# zikburner-r1.net
KiCad netlist of a schematic drawn in EAGLE
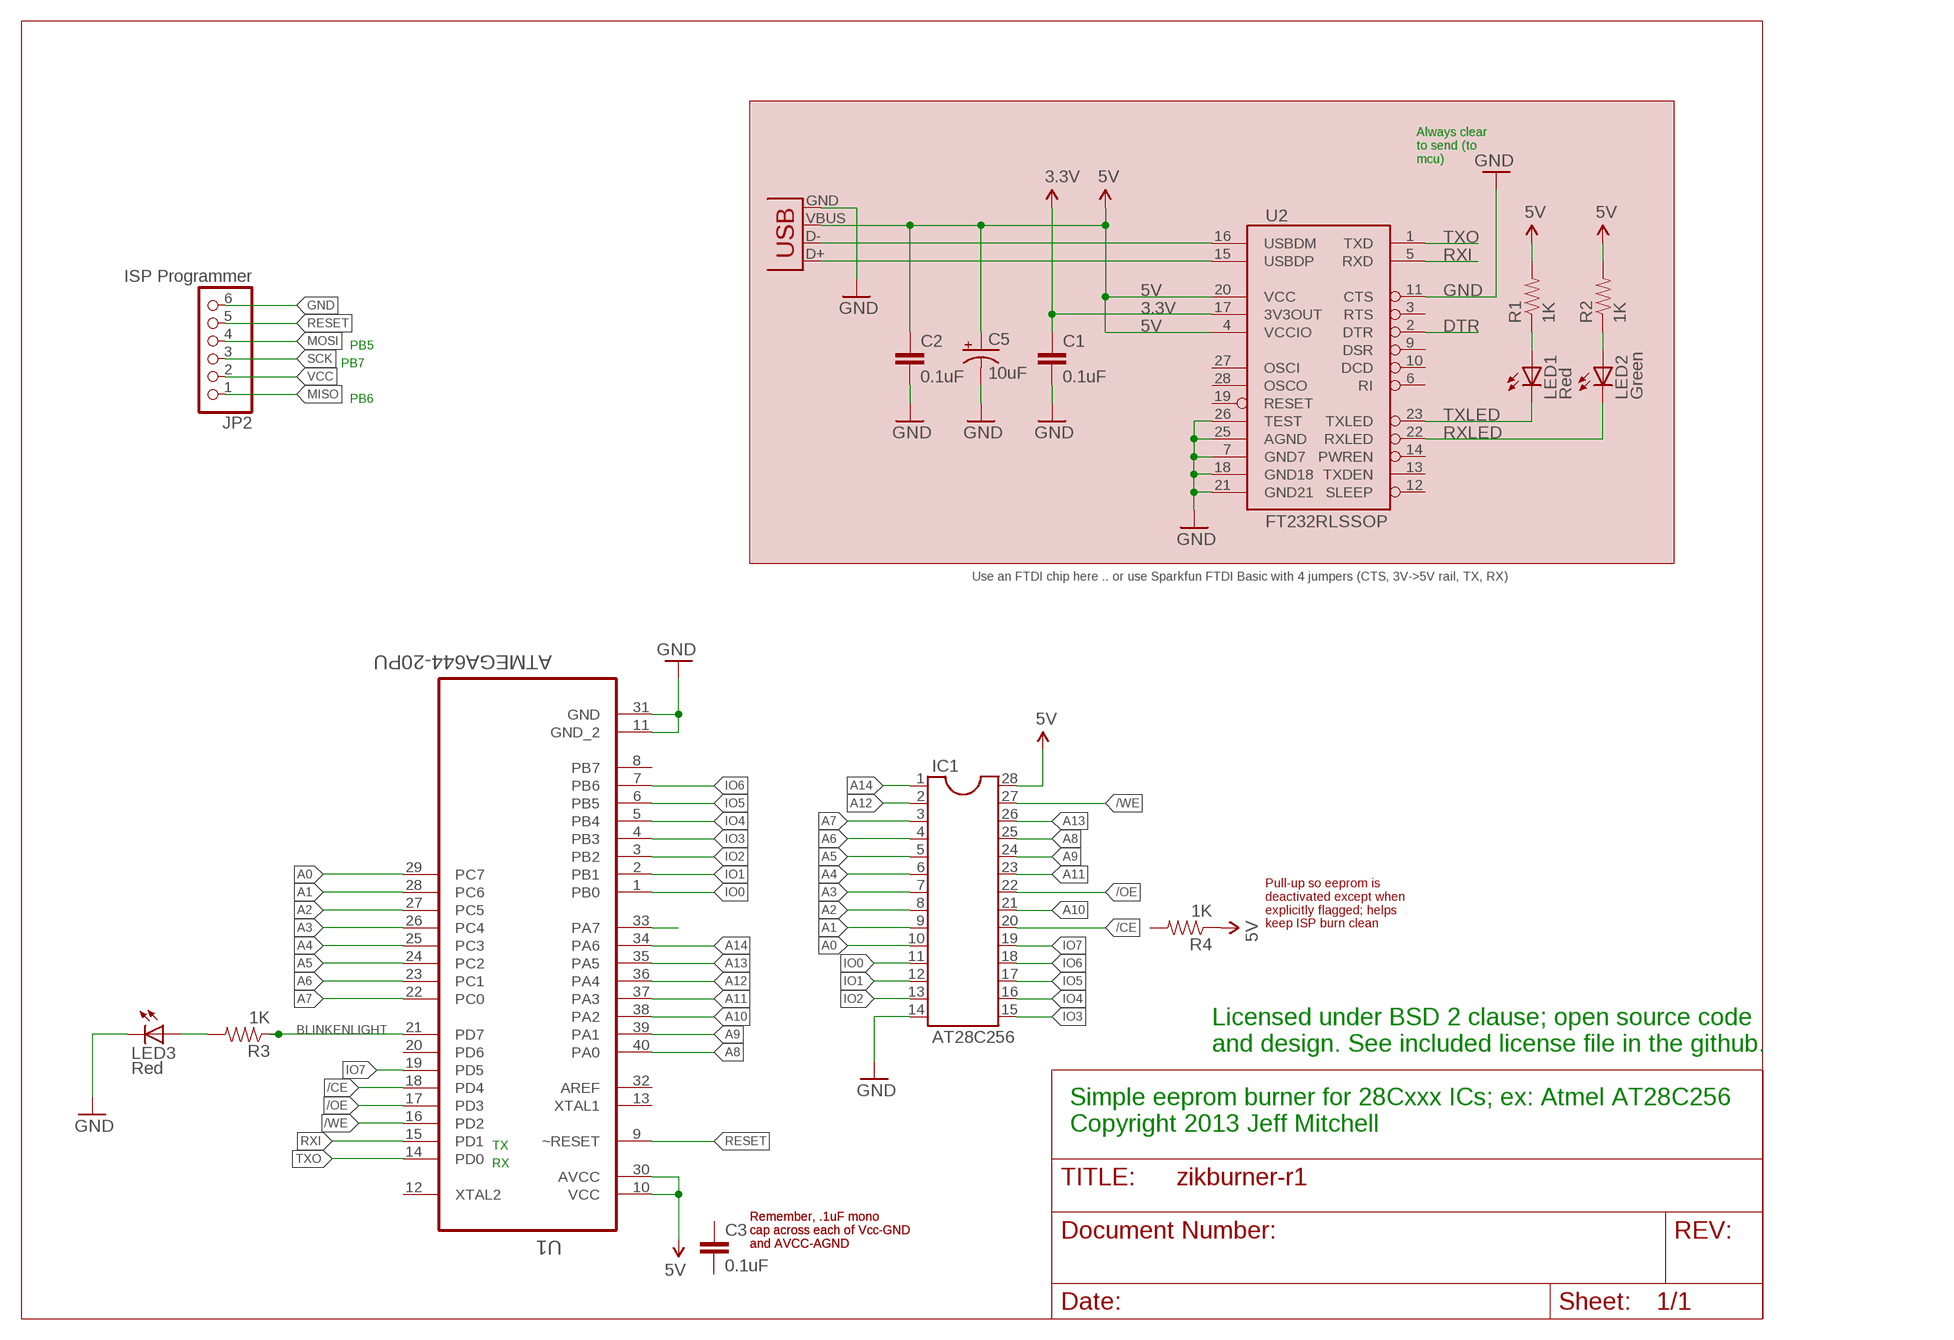
[diagram p0: schematic, sheet 1]

(export (version "E")
  (design (tool "Eeschema 10.0.6"))
  (components
    (comp (ref "C1")
      (value "0.1uF")
      (footprint "eagle-import:0402-CAP")
      (libsource (lib "eagle-import") (part "CAP0402-CAP"))
    )
    (comp (ref "C2")
      (value "0.1uF")
      (footprint "eagle-import:0402-CAP")
      (libsource (lib "eagle-import") (part "CAP0402-CAP"))
    )
    (comp (ref "C3")
      (value "0.1uF")
      (footprint "eagle-import:0402-CAP")
      (libsource (lib "eagle-import") (part "CAP0402-CAP"))
    )
    (comp (ref "C5")
      (value "10uF")
      (footprint "eagle-import:EIA3216")
      (libsource (lib "eagle-import") (part "CAP_POL1206"))
    )
    (comp (ref "IC1")
      (value "AT28C256")
      (footprint "eagle-import:DIL28-6")
      (libsource (lib "eagle-import") (part "DIL28"))
    )
    (comp (ref "JP2")
      (value "ISP Programmer")
      (footprint "eagle-import:1X06")
      (libsource (lib "eagle-import") (part "PINHD-1X6"))
    )
    (comp (ref "LED1")
      (value "Red")
      (footprint "eagle-import:LED-0603")
      (libsource (lib "eagle-import") (part "LED0603"))
    )
    (comp (ref "LED2")
      (value "Green")
      (footprint "eagle-import:LED-0603")
      (libsource (lib "eagle-import") (part "LED0603"))
    )
    (comp (ref "LED3")
      (value "Red")
      (footprint "eagle-import:LED-0603")
      (libsource (lib "eagle-import") (part "LED0603"))
    )
    (comp (ref "R1")
      (value "1K")
      (footprint "eagle-import:0402-RES")
      (libsource (lib "eagle-import") (part "RESISTOR0402-RES"))
    )
    (comp (ref "R2")
      (value "1K")
      (footprint "eagle-import:0402-RES")
      (libsource (lib "eagle-import") (part "RESISTOR0402-RES"))
    )
    (comp (ref "R3")
      (value "1K")
      (footprint "eagle-import:0402-RES")
      (libsource (lib "eagle-import") (part "RESISTOR0402-RES"))
    )
    (comp (ref "R4")
      (value "1K")
      (footprint "eagle-import:0402-RES")
      (libsource (lib "eagle-import") (part "RESISTOR0402-RES"))
    )
    (comp (ref "U1")
      (value "ATMEGA644-20PU")
      (footprint "eagle-import:DIP254P1524X482-40")
      (libsource (lib "eagle-import") (part "ATMEGA644-20PU"))
    )
    (comp (ref "U2")
      (value "FT232RLSSOP")
      (footprint "eagle-import:SSOP28DB")
      (libsource (lib "eagle-import") (part "FT232RLSSOP"))
    )
    (comp (ref "X2")
      (value "USB-SMD-NS")
      (footprint "eagle-import:USB-MINIB-NOSTOP")
      (libsource (lib "eagle-import") (part "USB-SMD-NS"))
    )
  )
  (nets
    (net (code "1") (name "/BLINKENLIGHT") (class "Default")
      (node (ref "R3") (pin "1") (pinfunction "1_1") (pintype "passive"))
      (node (ref "U1") (pin "21") (pinfunction "PD7_21") (pintype "bidirectional"))
    )
    (net (code "2") (name "/DTR") (class "Default")
      (node (ref "U2") (pin "2") (pinfunction "DTR_2") (pintype "output"))
    )
    (net (code "3") (name "/RXLED") (class "Default")
      (node (ref "LED2") (pin "C") (pinfunction "C_C") (pintype "passive"))
      (node (ref "U2") (pin "22") (pinfunction "RXLED_22") (pintype "input"))
    )
    (net (code "4") (name "/TXLED") (class "Default")
      (node (ref "LED1") (pin "C") (pinfunction "C_C") (pintype "passive"))
      (node (ref "U2") (pin "23") (pinfunction "TXLED_23") (pintype "input"))
    )
    (net (code "5") (name "3.3V") (class "Default")
      (node (ref "C1") (pin "1") (pinfunction "1_1") (pintype "passive"))
      (node (ref "U2") (pin "17") (pinfunction "3V3OUT_17") (pintype "output"))
    )
    (net (code "6") (name "5V") (class "Default")
      (node (ref "C2") (pin "1") (pinfunction "1_1") (pintype "passive"))
      (node (ref "C5") (pin "A") (pinfunction "+_A") (pintype "passive"))
      (node (ref "IC1") (pin "28") (pinfunction "28_28") (pintype "passive"))
      (node (ref "R1") (pin "2") (pinfunction "2_2") (pintype "passive"))
      (node (ref "R2") (pin "2") (pinfunction "2_2") (pintype "passive"))
      (node (ref "R4") (pin "1") (pinfunction "1_1") (pintype "passive"))
      (node (ref "U1") (pin "10") (pinfunction "VCC_10") (pintype "power_in"))
      (node (ref "U1") (pin "30") (pinfunction "AVCC_30") (pintype "power_in"))
      (node (ref "U2") (pin "20") (pinfunction "VCC_20") (pintype "power_in"))
      (node (ref "U2") (pin "4") (pinfunction "VCCIO_4") (pintype "power_in"))
      (node (ref "X2") (pin "VBUS") (pinfunction "VBUS_VBUS") (pintype "bidirectional"))
    )
    (net (code "7") (name "A0") (class "Default")
      (node (ref "IC1") (pin "10") (pinfunction "10_10") (pintype "passive"))
      (node (ref "U1") (pin "29") (pinfunction "PC7_29") (pintype "bidirectional"))
    )
    (net (code "8") (name "A1") (class "Default")
      (node (ref "IC1") (pin "9") (pinfunction "9_9") (pintype "passive"))
      (node (ref "U1") (pin "28") (pinfunction "PC6_28") (pintype "bidirectional"))
    )
    (net (code "9") (name "A2") (class "Default")
      (node (ref "IC1") (pin "8") (pinfunction "8_8") (pintype "passive"))
      (node (ref "U1") (pin "27") (pinfunction "PC5_27") (pintype "bidirectional"))
    )
    (net (code "10") (name "A3") (class "Default")
      (node (ref "IC1") (pin "7") (pinfunction "7_7") (pintype "passive"))
      (node (ref "U1") (pin "26") (pinfunction "PC4_26") (pintype "bidirectional"))
    )
    (net (code "11") (name "A4") (class "Default")
      (node (ref "IC1") (pin "6") (pinfunction "6_6") (pintype "passive"))
      (node (ref "U1") (pin "25") (pinfunction "PC3_25") (pintype "bidirectional"))
    )
    (net (code "12") (name "A5") (class "Default")
      (node (ref "IC1") (pin "5") (pinfunction "5_5") (pintype "passive"))
      (node (ref "U1") (pin "24") (pinfunction "PC2_24") (pintype "bidirectional"))
    )
    (net (code "13") (name "A6") (class "Default")
      (node (ref "IC1") (pin "4") (pinfunction "4_4") (pintype "passive"))
      (node (ref "U1") (pin "23") (pinfunction "PC1_23") (pintype "bidirectional"))
    )
    (net (code "14") (name "A7") (class "Default")
      (node (ref "IC1") (pin "3") (pinfunction "3_3") (pintype "passive"))
      (node (ref "U1") (pin "22") (pinfunction "PC0_22") (pintype "bidirectional"))
    )
    (net (code "15") (name "A8") (class "Default")
      (node (ref "IC1") (pin "25") (pinfunction "25_25") (pintype "passive"))
      (node (ref "U1") (pin "40") (pinfunction "PA0_40") (pintype "bidirectional"))
    )
    (net (code "16") (name "A9") (class "Default")
      (node (ref "IC1") (pin "24") (pinfunction "24_24") (pintype "passive"))
      (node (ref "U1") (pin "39") (pinfunction "PA1_39") (pintype "bidirectional"))
    )
    (net (code "17") (name "A10") (class "Default")
      (node (ref "IC1") (pin "21") (pinfunction "21_21") (pintype "passive"))
      (node (ref "U1") (pin "38") (pinfunction "PA2_38") (pintype "bidirectional"))
    )
    (net (code "18") (name "A11") (class "Default")
      (node (ref "IC1") (pin "23") (pinfunction "23_23") (pintype "passive"))
      (node (ref "U1") (pin "37") (pinfunction "PA3_37") (pintype "bidirectional"))
    )
    (net (code "19") (name "A12") (class "Default")
      (node (ref "IC1") (pin "2") (pinfunction "2_2") (pintype "passive"))
      (node (ref "U1") (pin "36") (pinfunction "PA4_36") (pintype "bidirectional"))
    )
    (net (code "20") (name "A13") (class "Default")
      (node (ref "IC1") (pin "26") (pinfunction "26_26") (pintype "passive"))
      (node (ref "U1") (pin "35") (pinfunction "PA5_35") (pintype "bidirectional"))
    )
    (net (code "21") (name "A14") (class "Default")
      (node (ref "IC1") (pin "1") (pinfunction "1_1") (pintype "passive"))
      (node (ref "U1") (pin "34") (pinfunction "PA6_34") (pintype "bidirectional"))
    )
    (net (code "22") (name "GND") (class "Default")
      (node (ref "C1") (pin "2") (pinfunction "2_2") (pintype "passive"))
      (node (ref "C2") (pin "2") (pinfunction "2_2") (pintype "passive"))
      (node (ref "C5") (pin "C") (pinfunction "-_C") (pintype "passive"))
      (node (ref "IC1") (pin "14") (pinfunction "14_14") (pintype "passive"))
      (node (ref "JP2") (pin "6") (pinfunction "6_6") (pintype "passive"))
      (node (ref "LED3") (pin "C") (pinfunction "C_C") (pintype "passive"))
      (node (ref "U1") (pin "11") (pinfunction "GND_2_11") (pintype "passive"))
      (node (ref "U1") (pin "31") (pinfunction "GND_31") (pintype "passive"))
      (node (ref "U2") (pin "11") (pinfunction "CTS_11") (pintype "input"))
      (node (ref "U2") (pin "18") (pinfunction "GND18_18") (pintype "power_in"))
      (node (ref "U2") (pin "21") (pinfunction "GND21_21") (pintype "power_in"))
      (node (ref "U2") (pin "25") (pinfunction "AGND_25") (pintype "power_in"))
      (node (ref "U2") (pin "26") (pinfunction "TEST_26") (pintype "input"))
      (node (ref "U2") (pin "7") (pinfunction "GND7_7") (pintype "power_in"))
      (node (ref "X2") (pin "GND") (pinfunction "GND_GND") (pintype "bidirectional"))
    )
    (net (code "23") (name "IO0") (class "Default")
      (node (ref "IC1") (pin "11") (pinfunction "11_11") (pintype "passive"))
      (node (ref "U1") (pin "1") (pinfunction "PB0_1") (pintype "bidirectional"))
    )
    (net (code "24") (name "IO1") (class "Default")
      (node (ref "IC1") (pin "12") (pinfunction "12_12") (pintype "passive"))
      (node (ref "U1") (pin "2") (pinfunction "PB1_2") (pintype "bidirectional"))
    )
    (net (code "25") (name "IO2") (class "Default")
      (node (ref "IC1") (pin "13") (pinfunction "13_13") (pintype "passive"))
      (node (ref "U1") (pin "3") (pinfunction "PB2_3") (pintype "bidirectional"))
    )
    (net (code "26") (name "IO3") (class "Default")
      (node (ref "IC1") (pin "15") (pinfunction "15_15") (pintype "passive"))
      (node (ref "U1") (pin "4") (pinfunction "PB3_4") (pintype "bidirectional"))
    )
    (net (code "27") (name "IO4") (class "Default")
      (node (ref "IC1") (pin "16") (pinfunction "16_16") (pintype "passive"))
      (node (ref "U1") (pin "5") (pinfunction "PB4_5") (pintype "bidirectional"))
    )
    (net (code "28") (name "IO5") (class "Default")
      (node (ref "IC1") (pin "17") (pinfunction "17_17") (pintype "passive"))
      (node (ref "U1") (pin "6") (pinfunction "PB5_6") (pintype "bidirectional"))
    )
    (net (code "29") (name "IO6") (class "Default")
      (node (ref "IC1") (pin "18") (pinfunction "18_18") (pintype "passive"))
      (node (ref "U1") (pin "7") (pinfunction "PB6_7") (pintype "bidirectional"))
    )
    (net (code "30") (name "IO7") (class "Default")
      (node (ref "IC1") (pin "19") (pinfunction "19_19") (pintype "passive"))
      (node (ref "U1") (pin "19") (pinfunction "PD5_19") (pintype "bidirectional"))
    )
    (net (code "31") (name "MISO") (class "Default")
      (node (ref "JP2") (pin "1") (pinfunction "1_1") (pintype "passive"))
    )
    (net (code "32") (name "MOSI") (class "Default")
      (node (ref "JP2") (pin "4") (pinfunction "4_4") (pintype "passive"))
    )
    (net (code "33") (name "Net-(LED1-PadA)") (class "Default")
      (node (ref "LED1") (pin "A") (pinfunction "A_A") (pintype "passive"))
      (node (ref "R1") (pin "1") (pinfunction "1_1") (pintype "passive"))
    )
    (net (code "34") (name "Net-(LED2-PadA)") (class "Default")
      (node (ref "LED2") (pin "A") (pinfunction "A_A") (pintype "passive"))
      (node (ref "R2") (pin "1") (pinfunction "1_1") (pintype "passive"))
    )
    (net (code "35") (name "Net-(LED3-PadA)") (class "Default")
      (node (ref "LED3") (pin "A") (pinfunction "A_A") (pintype "passive"))
      (node (ref "R3") (pin "2") (pinfunction "2_2") (pintype "passive"))
    )
    (net (code "36") (name "Net-(U2-USBDM)") (class "Default")
      (node (ref "U2") (pin "16") (pinfunction "USBDM_16") (pintype "bidirectional"))
      (node (ref "X2") (pin "D-") (pinfunction "D-_D-") (pintype "bidirectional"))
    )
    (net (code "37") (name "Net-(U2-USBDP)") (class "Default")
      (node (ref "U2") (pin "15") (pinfunction "USBDP_15") (pintype "bidirectional"))
      (node (ref "X2") (pin "D+") (pinfunction "D+_D+") (pintype "bidirectional"))
    )
    (net (code "38") (name "RESET") (class "Default")
      (node (ref "JP2") (pin "5") (pinfunction "5_5") (pintype "passive"))
      (node (ref "U1") (pin "9") (pinfunction "~{RESET}_9") (pintype "input"))
    )
    (net (code "39") (name "RXI") (class "Default")
      (node (ref "U1") (pin "15") (pinfunction "PD1_15") (pintype "bidirectional"))
      (node (ref "U2") (pin "5") (pinfunction "RXD_5") (pintype "input"))
    )
    (net (code "40") (name "SCK") (class "Default")
      (node (ref "JP2") (pin "3") (pinfunction "3_3") (pintype "passive"))
    )
    (net (code "41") (name "TXO") (class "Default")
      (node (ref "U1") (pin "14") (pinfunction "PD0_14") (pintype "bidirectional"))
      (node (ref "U2") (pin "1") (pinfunction "TXD_1") (pintype "output"))
    )
    (net (code "42") (name "VCC") (class "Default")
      (node (ref "JP2") (pin "2") (pinfunction "2_2") (pintype "passive"))
    )
    (net (code "43") (name "unconnected-(C3-Pad1)") (class "Default")
      (node (ref "C3") (pin "1") (pinfunction "1_1") (pintype "passive"))
    )
    (net (code "44") (name "unconnected-(C3-Pad2)") (class "Default")
      (node (ref "C3") (pin "2") (pinfunction "2_2") (pintype "passive"))
    )
    (net (code "45") (name "unconnected-(R4-Pad2)") (class "Default")
      (node (ref "R4") (pin "2") (pinfunction "2_2") (pintype "passive"))
    )
    (net (code "46") (name "unconnected-(U1-AREF-Pad32)") (class "Default")
      (node (ref "U1") (pin "32") (pinfunction "AREF_32") (pintype "input"))
    )
    (net (code "47") (name "unconnected-(U1-PA7-Pad33)") (class "Default")
      (node (ref "U1") (pin "33") (pinfunction "PA7_33") (pintype "bidirectional"))
    )
    (net (code "48") (name "unconnected-(U1-PB7-Pad8)") (class "Default")
      (node (ref "U1") (pin "8") (pinfunction "PB7_8") (pintype "bidirectional"))
    )
    (net (code "49") (name "unconnected-(U1-PD6-Pad20)") (class "Default")
      (node (ref "U1") (pin "20") (pinfunction "PD6_20") (pintype "bidirectional"))
    )
    (net (code "50") (name "unconnected-(U1-XTAL1-Pad13)") (class "Default")
      (node (ref "U1") (pin "13") (pinfunction "XTAL1_13") (pintype "input"))
    )
    (net (code "51") (name "unconnected-(U1-XTAL2-Pad12)") (class "Default")
      (node (ref "U1") (pin "12") (pinfunction "XTAL2_12") (pintype "output"))
    )
    (net (code "52") (name "unconnected-(U2-DCD-Pad10)") (class "Default")
      (node (ref "U2") (pin "10") (pinfunction "DCD_10") (pintype "input"))
    )
    (net (code "53") (name "unconnected-(U2-DSR-Pad9)") (class "Default")
      (node (ref "U2") (pin "9") (pinfunction "DSR_9") (pintype "input"))
    )
    (net (code "54") (name "unconnected-(U2-OSCI-Pad27)") (class "Default")
      (node (ref "U2") (pin "27") (pinfunction "OSCI_27") (pintype "input"))
    )
    (net (code "55") (name "unconnected-(U2-OSCO-Pad28)") (class "Default")
      (node (ref "U2") (pin "28") (pinfunction "OSCO_28") (pintype "output"))
    )
    (net (code "56") (name "unconnected-(U2-PWREN-Pad14)") (class "Default")
      (node (ref "U2") (pin "14") (pinfunction "PWREN_14") (pintype "input"))
    )
    (net (code "57") (name "unconnected-(U2-RESET-Pad19)") (class "Default")
      (node (ref "U2") (pin "19") (pinfunction "RESET_19") (pintype "input"))
    )
    (net (code "58") (name "unconnected-(U2-RI-Pad6)") (class "Default")
      (node (ref "U2") (pin "6") (pinfunction "RI_6") (pintype "input"))
    )
    (net (code "59") (name "unconnected-(U2-RTS-Pad3)") (class "Default")
      (node (ref "U2") (pin "3") (pinfunction "RTS_3") (pintype "output"))
    )
    (net (code "60") (name "unconnected-(U2-SLEEP-Pad12)") (class "Default")
      (node (ref "U2") (pin "12") (pinfunction "SLEEP_12") (pintype "input"))
    )
    (net (code "61") (name "unconnected-(U2-TXDEN-Pad13)") (class "Default")
      (node (ref "U2") (pin "13") (pinfunction "TXDEN_13") (pintype "input"))
    )
    (net (code "62") (name "{slash}CE") (class "Default")
      (node (ref "IC1") (pin "20") (pinfunction "20_20") (pintype "passive"))
      (node (ref "U1") (pin "18") (pinfunction "PD4_18") (pintype "bidirectional"))
    )
    (net (code "63") (name "{slash}OE") (class "Default")
      (node (ref "IC1") (pin "22") (pinfunction "22_22") (pintype "passive"))
      (node (ref "U1") (pin "17") (pinfunction "PD3_17") (pintype "bidirectional"))
    )
    (net (code "64") (name "{slash}WE") (class "Default")
      (node (ref "IC1") (pin "27") (pinfunction "27_27") (pintype "passive"))
      (node (ref "U1") (pin "16") (pinfunction "PD2_16") (pintype "bidirectional"))
    )
  )
)
